# Ultrasonic_Transducer.net
KiCad netlist of a schematic drawn in Altium Designer
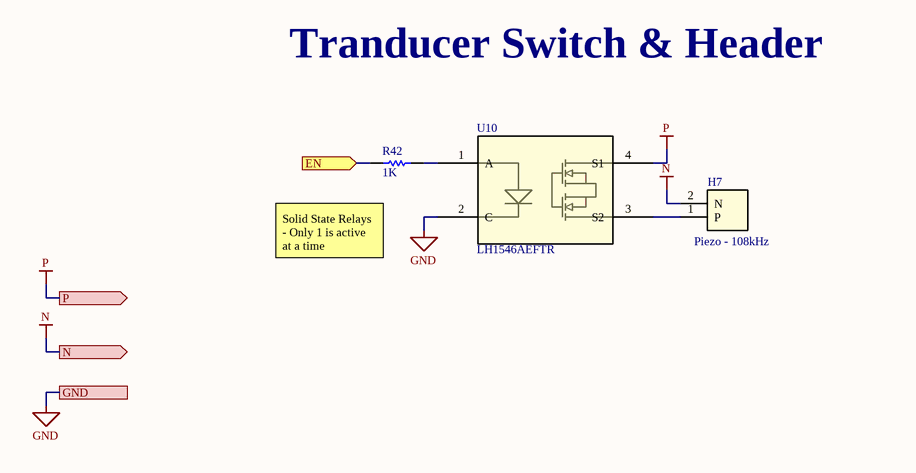
[diagram p0: Ultrasonic_Transducer.SchDoc]

(export (version "E")
  (design (tool "Eeschema 10.0.6"))
  (components
    (comp (ref "H7")
      (value "Piezo - 108kHz")
      (footprint "JST_B2B-PH-K-S")
      (description "CONN HDR 2POS 0.1 TIN PCB")
      (libsource (lib "Diffuser") (part "2 Pin Male 2mm"))
    )
    (comp (ref "R42")
      (value "1K")
      (footprint "R_0603")
      (description "RES 1K OHM 1% 1/10W 0603")
      (libsource (lib "Diffuser") (part "RS_1K"))
    )
    (comp (ref "U10")
      (value "LH1546AEFTR")
      (footprint "SO_6AEFTR_VIS-M")
      (description "Solid State SPST-NO (1 Form A) 4-SOP (0.173\", 4.40mm)")
      (fields (field (name "COPYRIGHT") "Copyright (C) 2024 Ultra Librarian. All rights reserved."))
      (libsource (lib "Diffuser") (part "LH1546AEFTR"))
    )
  )
  (nets
    (net (code "1") (name "/EN") (class "Default")
      (node (ref "R42") (pin "1") (pinfunction "1_1") (pintype "passive"))
    )
    (net (code "2") (name "GND") (class "Default")
      (node (ref "U10") (pin "2") (pinfunction "C_2") (pintype "passive"))
    )
    (net (code "3") (name "N") (class "Default")
      (node (ref "H7") (pin "2") (pinfunction "N_2") (pintype "passive"))
    )
    (net (code "4") (name "Net-(H7-P)") (class "Default")
      (node (ref "H7") (pin "1") (pinfunction "P_1") (pintype "passive"))
      (node (ref "U10") (pin "3") (pinfunction "S2_3") (pintype "passive"))
    )
    (net (code "5") (name "Net-(U10-A)") (class "Default")
      (node (ref "R42") (pin "2") (pinfunction "2_2") (pintype "passive"))
      (node (ref "U10") (pin "1") (pinfunction "A_1") (pintype "passive"))
    )
    (net (code "6") (name "P") (class "Default")
      (node (ref "U10") (pin "4") (pinfunction "S1_4") (pintype "passive"))
    )
  )
)
